# IR_Badge_2018.net
KiCad netlist of a schematic drawn in EAGLE
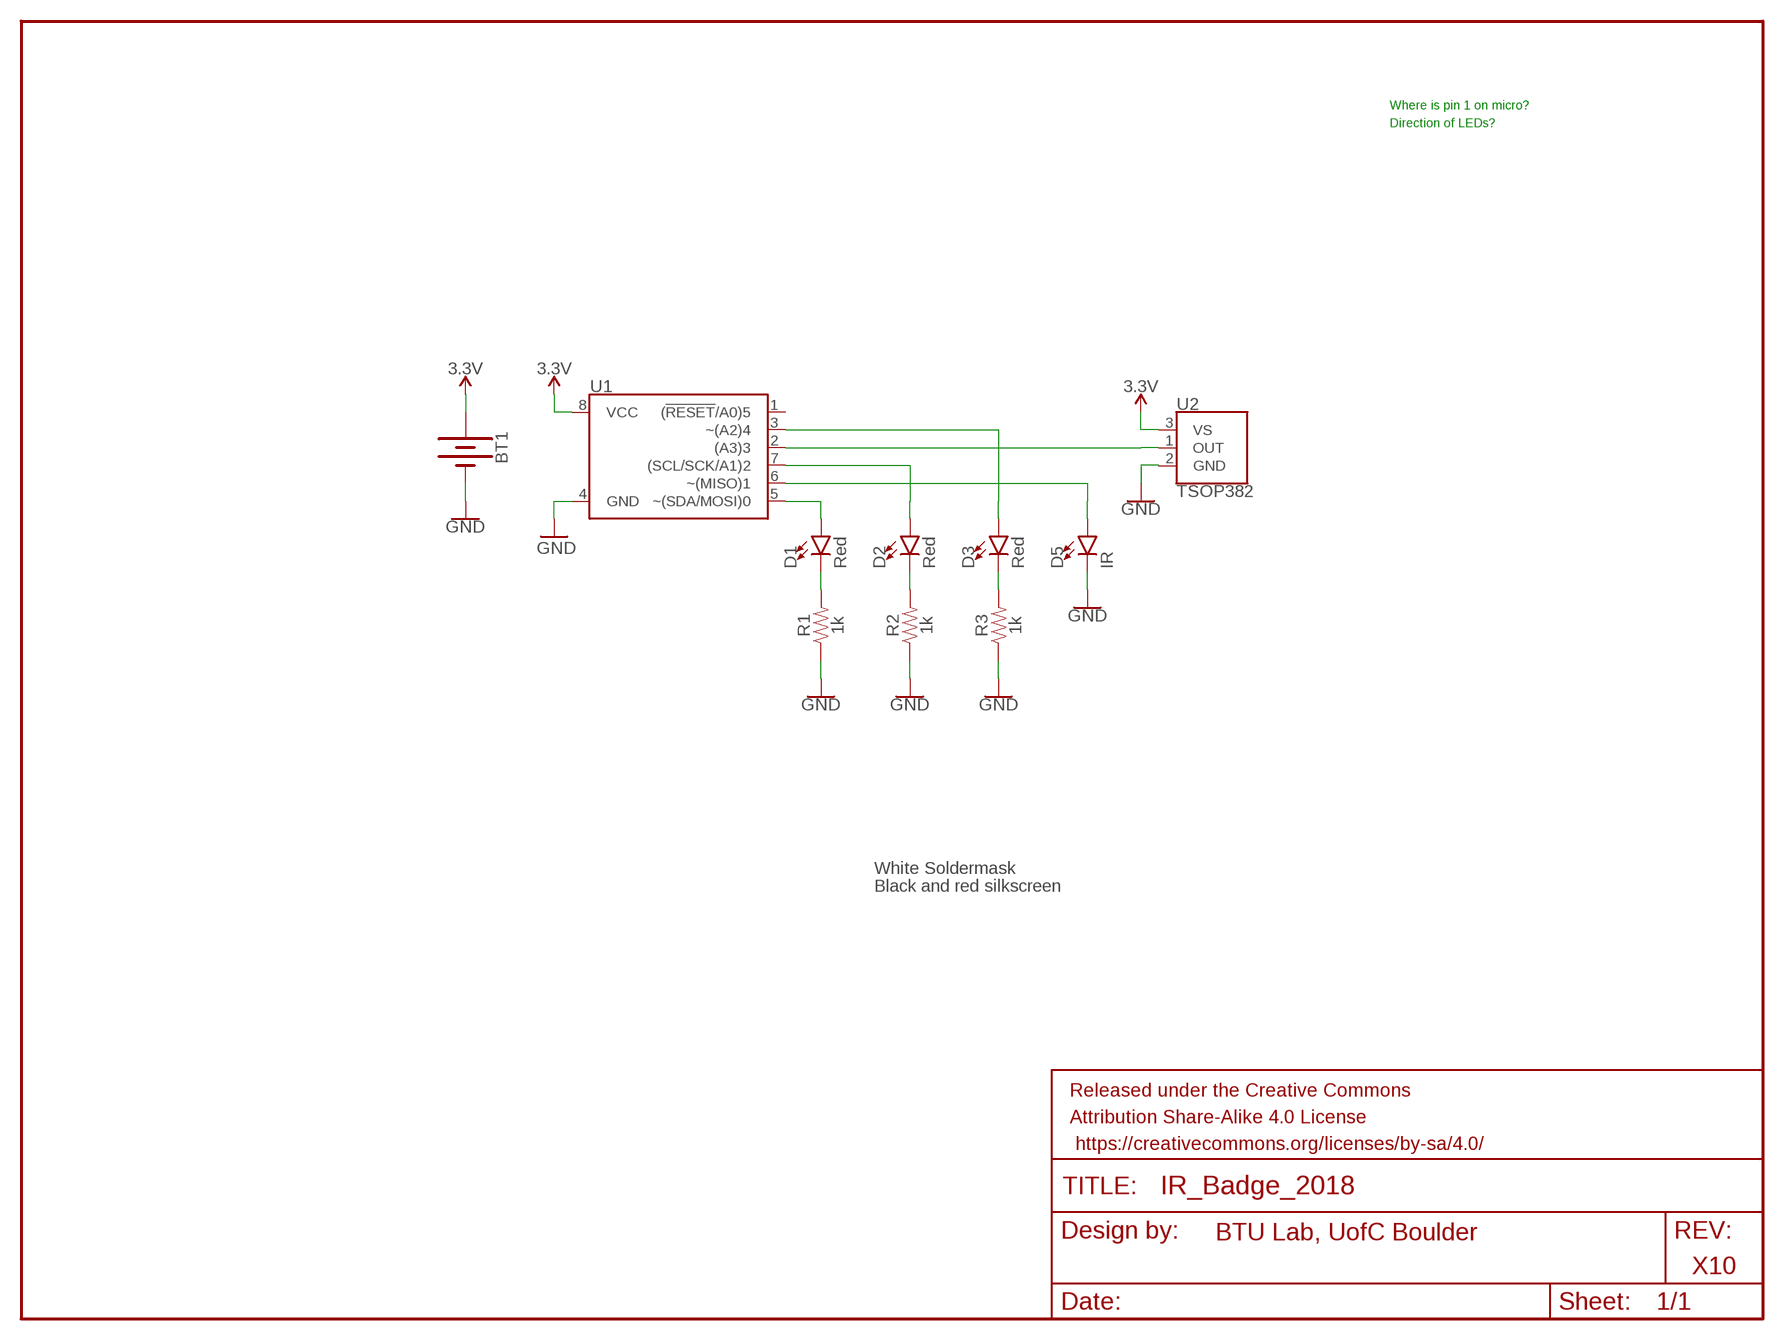
[diagram p0: schematic, sheet 1]

(export (version "E")
  (design (tool "Eeschema 10.0.6"))
  (components
    (comp (ref "BT1")
      (value "BATTERY-20MM_PTH")
      (footprint "eagle-import:BATTCOM_20MM_PTH")
      (libsource (lib "eagle-import") (part "BATTERY-20MM_PTH"))
    )
    (comp (ref "D1")
      (value "Red")
      (footprint "eagle-import:LED_5MM_EXTRASILK")
      (libsource (lib "eagle-import") (part "LEDRED"))
    )
    (comp (ref "D2")
      (value "Red")
      (footprint "eagle-import:LED_5MM_EXTRASILK")
      (libsource (lib "eagle-import") (part "LEDRED"))
    )
    (comp (ref "D3")
      (value "Red")
      (footprint "eagle-import:LED_5MM_EXTRASILK")
      (libsource (lib "eagle-import") (part "LEDRED"))
    )
    (comp (ref "D5")
      (value "IR")
      (footprint "eagle-import:LED_5MM_NOSILK")
      (libsource (lib "eagle-import") (part "LEDNS"))
    )
    (comp (ref "FRAME1")
      (value "FRAME-LETTER")
      (footprint "eagle-import:CREATIVE_COMMONS")
      (libsource (lib "eagle-import") (part "FRAME-LETTER"))
    )
    (comp (ref "R1")
      (value "1k")
      (footprint "eagle-import:RESISTOR")
      (libsource (lib "eagle-import") (part "RESISTOR"))
    )
    (comp (ref "R2")
      (value "1k")
      (footprint "eagle-import:RESISTOR")
      (libsource (lib "eagle-import") (part "RESISTOR"))
    )
    (comp (ref "R3")
      (value "1k")
      (footprint "eagle-import:RESISTOR")
      (libsource (lib "eagle-import") (part "RESISTOR"))
    )
    (comp (ref "U1")
      (value "ATTINY85-ARDUINODIP")
      (footprint "eagle-import:DIP-8")
      (libsource (lib "eagle-import") (part "ATTINY85-ARDUINODIP"))
    )
    (comp (ref "U2")
      (value "TSOP382")
      (footprint "eagle-import:TSOP382-HORIZONTAL")
      (libsource (lib "eagle-import") (part "TSOP382"))
    )
  )
  (nets
    (net (code "1") (name "3.3V") (class "Default")
      (node (ref "BT1") (pin "1") (pinfunction "+_1") (pintype "power_in"))
      (node (ref "U1") (pin "8") (pinfunction "VCC_8") (pintype "bidirectional"))
      (node (ref "U2") (pin "3") (pinfunction "VS_3") (pintype "bidirectional"))
    )
    (net (code "2") (name "GND") (class "Default")
      (node (ref "BT1") (pin "2") (pinfunction "-_2") (pintype "power_in"))
      (node (ref "D5") (pin "K") (pinfunction "C_K") (pintype "passive"))
      (node (ref "R1") (pin "P$1") (pinfunction "1_P$1") (pintype "passive"))
      (node (ref "R2") (pin "P$1") (pinfunction "1_P$1") (pintype "passive"))
      (node (ref "R3") (pin "P$1") (pinfunction "1_P$1") (pintype "passive"))
      (node (ref "U1") (pin "4") (pinfunction "GND_4") (pintype "bidirectional"))
      (node (ref "U2") (pin "2") (pinfunction "GND_2") (pintype "bidirectional"))
    )
    (net (code "3") (name "Net-(D1-C)") (class "Default")
      (node (ref "D1") (pin "K") (pinfunction "C_K") (pintype "passive"))
      (node (ref "R1") (pin "P$2") (pinfunction "2_P$2") (pintype "passive"))
    )
    (net (code "4") (name "Net-(D2-C)") (class "Default")
      (node (ref "D2") (pin "K") (pinfunction "C_K") (pintype "passive"))
      (node (ref "R2") (pin "P$2") (pinfunction "2_P$2") (pintype "passive"))
    )
    (net (code "5") (name "Net-(D3-C)") (class "Default")
      (node (ref "D3") (pin "K") (pinfunction "C_K") (pintype "passive"))
      (node (ref "R3") (pin "P$2") (pinfunction "2_P$2") (pintype "passive"))
    )
    (net (code "6") (name "Net-(U1-(A3)3)") (class "Default")
      (node (ref "U1") (pin "2") (pinfunction "(A3)3_2") (pintype "bidirectional"))
      (node (ref "U2") (pin "1") (pinfunction "OUT_1") (pintype "bidirectional"))
    )
    (net (code "7") (name "Net-(U1-(SCL{slash}SCK{slash}A1)2)") (class "Default")
      (node (ref "D2") (pin "A") (pinfunction "A_A") (pintype "passive"))
      (node (ref "U1") (pin "7") (pinfunction "(SCL/SCK/A1)2_7") (pintype "bidirectional"))
    )
    (net (code "8") (name "Net-(U1-~{(A2})4)") (class "Default")
      (node (ref "D3") (pin "A") (pinfunction "A_A") (pintype "passive"))
      (node (ref "U1") (pin "3") (pinfunction "~{(A2})4_3") (pintype "bidirectional"))
    )
    (net (code "9") (name "Net-(U1-~{(MISO})1)") (class "Default")
      (node (ref "D5") (pin "A") (pinfunction "A_A") (pintype "passive"))
      (node (ref "U1") (pin "6") (pinfunction "~{(MISO})1_6") (pintype "bidirectional"))
    )
    (net (code "10") (name "Net-(U1-~{(SDA{slash}MOSI})0)") (class "Default")
      (node (ref "D1") (pin "A") (pinfunction "A_A") (pintype "passive"))
      (node (ref "U1") (pin "5") (pinfunction "~{(SDA/MOSI})0_5") (pintype "bidirectional"))
    )
    (net (code "11") (name "unconnected-(U1-(~{RESET}{slash}A0)5-Pad1)") (class "Default")
      (node (ref "U1") (pin "1") (pinfunction "(~{RESET}/A0)5_1") (pintype "bidirectional"))
    )
  )
)
